# Spindle_Sync.net
KiCad netlist of a schematic drawn in Altium Designer
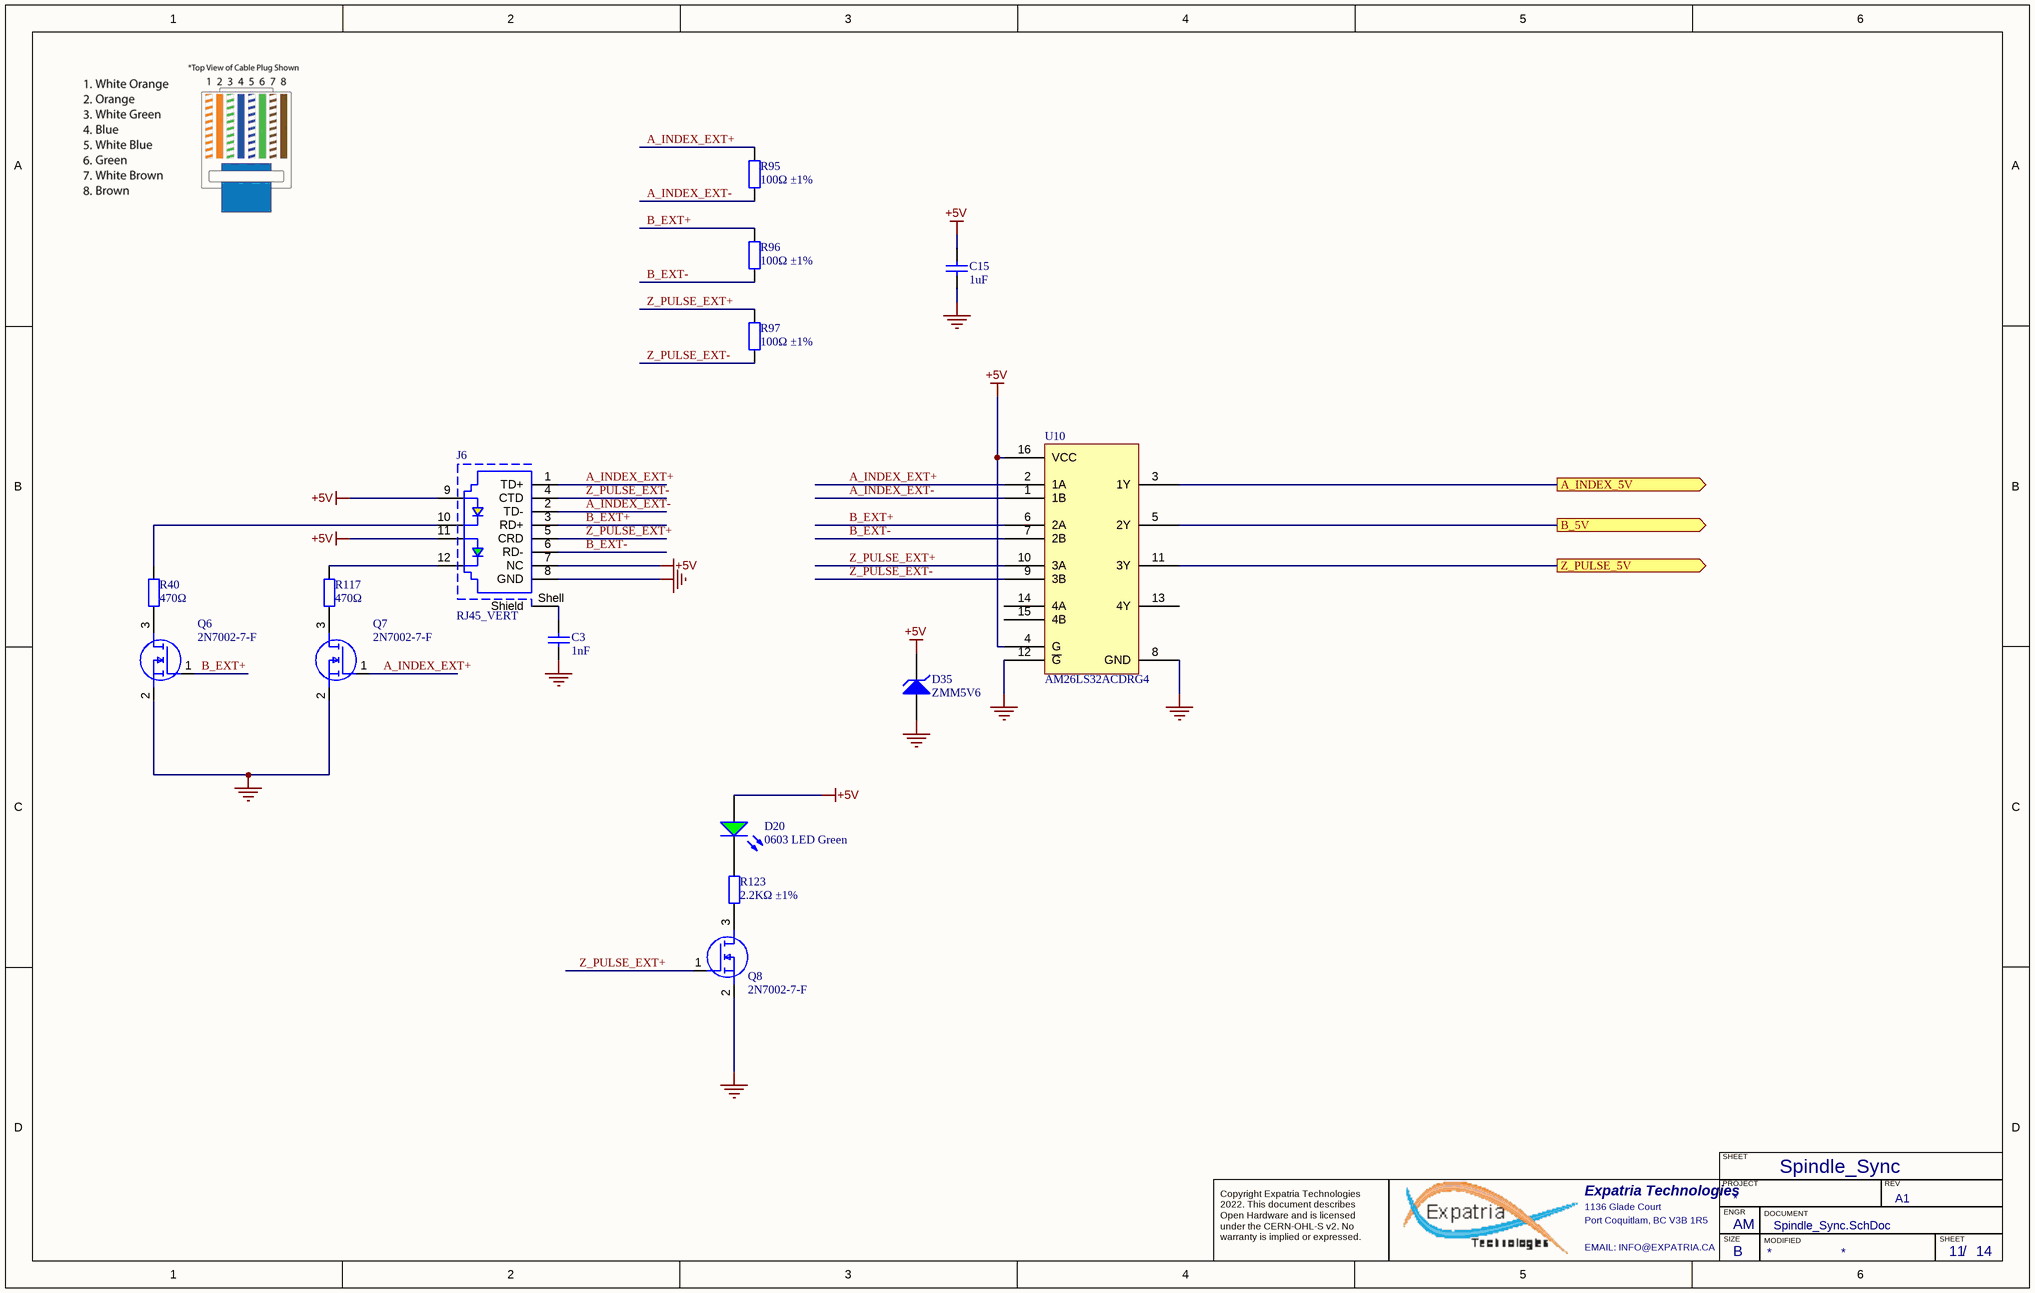
[diagram p0: Spindle_Sync.SchDoc]

(export (version "E")
  (design (tool "Eeschema 10.0.6"))
  (components
    (comp (ref "C3")
      (value "1nF")
      (footprint "0603_C")
      (description "Chip capacitors")
      (fields
        (field (name "MANUFACTURER") "Samsung Electro-Mechanics")
        (field (name "PARTNUMBER") "CL10B102KB8NNNC")
      )
      (libsource (lib "Cap") (part "0603 1nF (102) 10% 50V"))
    )
    (comp (ref "C15")
      (value "1uF")
      (footprint "0603_C")
      (description "Chip capacitors")
      (fields
        (field (name "MANUFACTURER") "Samsung Electro-Mechanics")
        (field (name "PARTNUMBER") "CL10A105KB8NNNC")
      )
      (libsource (lib "Cap") (part "0603 1uF (105) 10% 50V"))
    )
    (comp (ref "D20")
      (value "0603 LED Green")
      (footprint "0603_LED_S1 - GREEN")
      (fields
        (field (name "MANUFACTURER PART NUMBER") "19-217/GHC-YR1S2/3T")
        (field (name "MANUFACTURER") "Everlight Elec")
      )
      (libsource (lib "Sienci_Labs") (part "19-217/GHC-YR1S2/3T"))
    )
    (comp (ref "D35")
      (value "ZMM5V6")
      (footprint "LL-34")
      (description "500mW - 0.1uA @ 1V 5.6V LL-34 Zener Diodes ROHS")
      (libsource (lib "Zener") (part "LL-34 ZMM5V6"))
    )
    (comp (ref "J6")
      (value "RJ45_VERT")
      (footprint "74990101210")
      (description "Telecom and Datacom Connector, 8 Contact(s), Female, Straight, Solder Terminal")
      (libsource (lib "Cambridge Mobile Telematics, Inc") (part "74990101210"))
    )
    (comp (ref "Q6")
      (value "2N7002-7-F")
      (footprint "SOT-23(SOT-23-3)")
      (description "60V 115mA 7.5Ω@5V,50mA 370mW N Channel SOT-23 MOSFETs ROHS")
      (fields (field (name "MANUFACTURER") "Diodes Inc.") (field (name "MOUSER PART NUMBER") "621-2N7002-F"))
      (libsource (lib "Sienci_Labs") (part "2N7002-7-F"))
    )
    (comp (ref "Q7")
      (value "2N7002-7-F")
      (footprint "SOT-23(SOT-23-3)")
      (description "60V 115mA 7.5Ω@5V,50mA 370mW N Channel SOT-23 MOSFETs ROHS")
      (fields (field (name "MANUFACTURER") "Diodes Inc.") (field (name "MOUSER PART NUMBER") "621-2N7002-F"))
      (libsource (lib "Sienci_Labs") (part "2N7002-7-F"))
    )
    (comp (ref "Q8")
      (value "2N7002-7-F")
      (footprint "SOT-23(SOT-23-3)")
      (description "60V 115mA 7.5Ω@5V,50mA 370mW N Channel SOT-23 MOSFETs ROHS")
      (fields (field (name "MANUFACTURER") "Diodes Inc.") (field (name "MOUSER PART NUMBER") "621-2N7002-F"))
      (libsource (lib "Sienci_Labs") (part "2N7002-7-F"))
    )
    (comp (ref "R40")
      (value "470Ω ±1%")
      (footprint "0402_R")
      (description "Chip resistor")
      (fields
        (field (name "TOLERANCE") "1%")
        (field (name "POWER") "1/16W")
        (field (name "RESISTANCE") "470Ω")
      )
      (libsource (lib "RES") (part "0402 470R (4700) 1%"))
    )
    (comp (ref "R95")
      (value "100Ω ±1%")
      (footprint "0402_R")
      (description "Chip resistor")
      (fields (field (name "MANUFACTURER") "Uniroyal Elec") (field (name "PARTNUMBER") "0402WGF1000TCE"))
      (libsource (lib "RES") (part "0402 100R (1000) 1%"))
    )
    (comp (ref "R96")
      (value "100Ω ±1%")
      (footprint "0402_R")
      (description "Chip resistor")
      (fields (field (name "MANUFACTURER") "Uniroyal Elec") (field (name "PARTNUMBER") "0402WGF1000TCE"))
      (libsource (lib "RES") (part "0402 100R (1000) 1%"))
    )
    (comp (ref "R97")
      (value "100Ω ±1%")
      (footprint "0402_R")
      (description "Chip resistor")
      (fields (field (name "MANUFACTURER") "Uniroyal Elec") (field (name "PARTNUMBER") "0402WGF1000TCE"))
      (libsource (lib "RES") (part "0402 100R (1000) 1%"))
    )
    (comp (ref "R117")
      (value "470Ω ±1%")
      (footprint "0402_R")
      (description "Chip resistor")
      (fields
        (field (name "TOLERANCE") "1%")
        (field (name "POWER") "1/16W")
        (field (name "RESISTANCE") "470Ω")
      )
      (libsource (lib "RES") (part "0402 470R (4700) 1%"))
    )
    (comp (ref "R123")
      (value "2.2KΩ ±1%")
      (footprint "0402_R")
      (description "Chip resistor")
      (fields (field (name "MANUFACTURER") "Uniroyal Elec") (field (name "POWER") "1/16W"))
      (libsource (lib "RES") (part "0402 2.2K (2201) 1%"))
    )
    (comp (ref "U10")
      (value "AM26LS32ACDRG4")
      (footprint "SOIC-16_150mil")
      (description "RS-422 Interface IC Quad Diff Line Rcvr")
      (libsource (lib "IC") (part "AM26LS32ACDRG4_[C6180]"))
    )
  )
  (nets
    (net (code "1") (name "+5V") (class "Default")
      (node (ref "C15") (pin "2") (pinfunction "2_2") (pintype "passive"))
      (node (ref "D20") (pin "A") (pinfunction "A_A") (pintype "passive"))
      (node (ref "D35") (pin "2") (pinfunction "K_2") (pintype "passive"))
      (node (ref "J6") (pin "11") (pinfunction "11_11") (pintype "passive"))
      (node (ref "J6") (pin "7") (pinfunction "NC_7") (pintype "passive"))
      (node (ref "J6") (pin "9") (pinfunction "9_9") (pintype "passive"))
      (node (ref "U10") (pin "16") (pinfunction "VCC_16") (pintype "passive"))
      (node (ref "U10") (pin "4") (pinfunction "G_4") (pintype "passive"))
    )
    (net (code "2") (name "/A_INDEX_5V") (class "Default")
      (node (ref "U10") (pin "3") (pinfunction "1Y_3") (pintype "passive"))
    )
    (net (code "3") (name "/A_INDEX_EXT+") (class "Default")
      (node (ref "J6") (pin "1") (pinfunction "TD+_1") (pintype "passive"))
      (node (ref "Q7") (pin "1") (pinfunction "G_1") (pintype "passive"))
      (node (ref "R95") (pin "2") (pinfunction "2_2") (pintype "passive"))
      (node (ref "U10") (pin "2") (pinfunction "1A_2") (pintype "passive"))
    )
    (net (code "4") (name "/A_INDEX_EXT-") (class "Default")
      (node (ref "J6") (pin "2") (pinfunction "TD-_2") (pintype "passive"))
      (node (ref "R95") (pin "1") (pinfunction "1_1") (pintype "passive"))
      (node (ref "U10") (pin "1") (pinfunction "1B_1") (pintype "passive"))
    )
    (net (code "5") (name "/B_5V") (class "Default")
      (node (ref "U10") (pin "5") (pinfunction "2Y_5") (pintype "passive"))
    )
    (net (code "6") (name "/B_EXT+") (class "Default")
      (node (ref "J6") (pin "3") (pinfunction "RD+_3") (pintype "passive"))
      (node (ref "Q6") (pin "1") (pinfunction "G_1") (pintype "passive"))
      (node (ref "R96") (pin "2") (pinfunction "2_2") (pintype "passive"))
      (node (ref "U10") (pin "6") (pinfunction "2A_6") (pintype "passive"))
    )
    (net (code "7") (name "/B_EXT-") (class "Default")
      (node (ref "J6") (pin "6") (pinfunction "RD-_6") (pintype "passive"))
      (node (ref "R96") (pin "1") (pinfunction "1_1") (pintype "passive"))
      (node (ref "U10") (pin "7") (pinfunction "2B_7") (pintype "passive"))
    )
    (net (code "8") (name "/Z_PULSE_5V") (class "Default")
      (node (ref "U10") (pin "11") (pinfunction "3Y_11") (pintype "passive"))
    )
    (net (code "9") (name "/Z_PULSE_EXT+") (class "Default")
      (node (ref "J6") (pin "5") (pinfunction "CRD_5") (pintype "passive"))
      (node (ref "Q8") (pin "1") (pinfunction "G_1") (pintype "passive"))
      (node (ref "R97") (pin "2") (pinfunction "2_2") (pintype "passive"))
      (node (ref "U10") (pin "10") (pinfunction "3A_10") (pintype "passive"))
    )
    (net (code "10") (name "/Z_PULSE_EXT-") (class "Default")
      (node (ref "J6") (pin "4") (pinfunction "CTD_4") (pintype "passive"))
      (node (ref "R97") (pin "1") (pinfunction "1_1") (pintype "passive"))
      (node (ref "U10") (pin "9") (pinfunction "3B_9") (pintype "passive"))
    )
    (net (code "11") (name "GND") (class "Default")
      (node (ref "C15") (pin "1") (pinfunction "1_1") (pintype "passive"))
      (node (ref "C3") (pin "1") (pinfunction "1_1") (pintype "passive"))
      (node (ref "D35") (pin "1") (pinfunction "A_1") (pintype "passive"))
      (node (ref "J6") (pin "8") (pinfunction "GND_8") (pintype "passive"))
      (node (ref "Q6") (pin "2") (pinfunction "S_2") (pintype "passive"))
      (node (ref "Q7") (pin "2") (pinfunction "S_2") (pintype "passive"))
      (node (ref "Q8") (pin "2") (pinfunction "S_2") (pintype "passive"))
      (node (ref "U10") (pin "12") (pinfunction "~{G}_12") (pintype "passive"))
      (node (ref "U10") (pin "8") (pinfunction "GND_8") (pintype "passive"))
    )
    (net (code "12") (name "Net-(D20-PadK)") (class "Default")
      (node (ref "D20") (pin "K") (pinfunction "K_K") (pintype "passive"))
      (node (ref "R123") (pin "2") (pinfunction "2_2") (pintype "passive"))
    )
    (net (code "13") (name "Net-(J6-Pad10)") (class "Default")
      (node (ref "J6") (pin "10") (pinfunction "10_10") (pintype "passive"))
      (node (ref "R40") (pin "2") (pinfunction "2_2") (pintype "passive"))
    )
    (net (code "14") (name "Net-(J6-Pad12)") (class "Default")
      (node (ref "J6") (pin "12") (pinfunction "12_12") (pintype "passive"))
      (node (ref "R117") (pin "2") (pinfunction "2_2") (pintype "passive"))
    )
    (net (code "15") (name "Net-(J6-Shield)") (class "Default")
      (node (ref "C3") (pin "2") (pinfunction "2_2") (pintype "passive"))
      (node (ref "J6") (pin "Shell") (pinfunction "Shield_Shell") (pintype "passive"))
    )
    (net (code "16") (name "Net-(Q6-D)") (class "Default")
      (node (ref "Q6") (pin "3") (pinfunction "D_3") (pintype "passive"))
      (node (ref "R40") (pin "1") (pinfunction "1_1") (pintype "passive"))
    )
    (net (code "17") (name "Net-(Q7-D)") (class "Default")
      (node (ref "Q7") (pin "3") (pinfunction "D_3") (pintype "passive"))
      (node (ref "R117") (pin "1") (pinfunction "1_1") (pintype "passive"))
    )
    (net (code "18") (name "Net-(Q8-D)") (class "Default")
      (node (ref "Q8") (pin "3") (pinfunction "D_3") (pintype "passive"))
      (node (ref "R123") (pin "1") (pinfunction "1_1") (pintype "passive"))
    )
    (net (code "19") (name "unconnected-(U10-4A-Pad14)") (class "Default")
      (node (ref "U10") (pin "14") (pinfunction "4A_14") (pintype "passive"))
    )
    (net (code "20") (name "unconnected-(U10-4B-Pad15)") (class "Default")
      (node (ref "U10") (pin "15") (pinfunction "4B_15") (pintype "passive"))
    )
    (net (code "21") (name "unconnected-(U10-4Y-Pad13)") (class "Default")
      (node (ref "U10") (pin "13") (pinfunction "4Y_13") (pintype "passive"))
    )
  )
)
